# Blank_V3_2.net
KiCad netlist of a schematic drawn in EAGLE
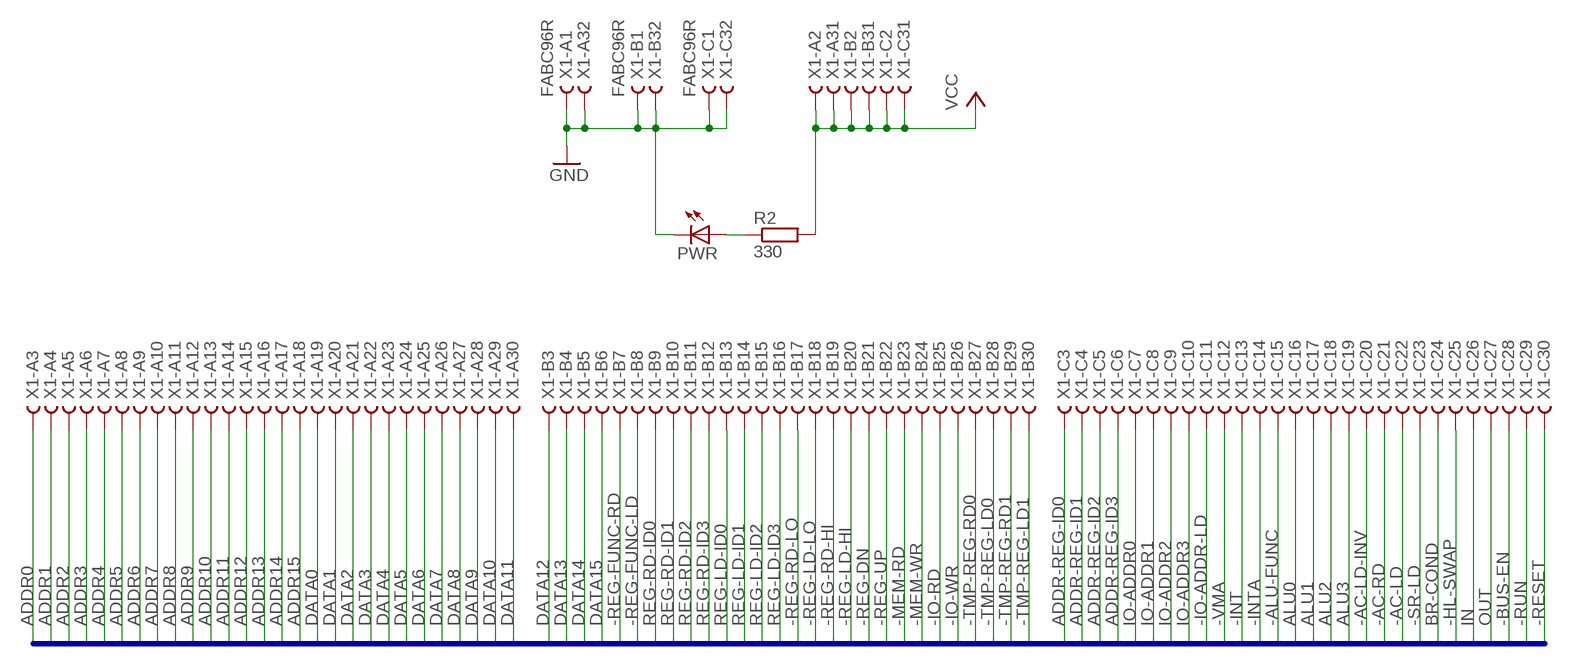
[diagram p0: schematic, sheet 1]

(export (version "E")
  (design (tool "Eeschema 10.0.6"))
  (components
    (comp (ref "PWR")
      (value "LED5MM")
      (footprint "eagle-import:LED5MM")
      (libsource (lib "eagle-import") (part "LED5MM"))
    )
    (comp (ref "R2")
      (value "330")
      (footprint "eagle-import:0207_10")
      (libsource (lib "eagle-import") (part "R0207/10"))
    )
    (comp (ref "X1")
      (value "FABC96R")
      (footprint "eagle-import:FABC96R")
      (libsource (lib "eagle-import") (part "FABC96R"))
    )
  )
  (nets
    (net (code "1") (name "/-AC-LD") (class "Default")
      (node (ref "X1") (pin "C22") (pinfunction "B_C22") (pintype "passive"))
    )
    (net (code "2") (name "/-AC-LD-INV") (class "Default")
      (node (ref "X1") (pin "C20") (pinfunction "B_C20") (pintype "passive"))
    )
    (net (code "3") (name "/-AC-RD") (class "Default")
      (node (ref "X1") (pin "C21") (pinfunction "B_C21") (pintype "passive"))
    )
    (net (code "4") (name "/-ALU-FUNC") (class "Default")
      (node (ref "X1") (pin "C15") (pinfunction "B_C15") (pintype "passive"))
    )
    (net (code "5") (name "/-BUS-EN") (class "Default")
      (node (ref "X1") (pin "C28") (pinfunction "B_C28") (pintype "passive"))
    )
    (net (code "6") (name "/-HL-SWAP") (class "Default")
      (node (ref "X1") (pin "C25") (pinfunction "B_C25") (pintype "passive"))
    )
    (net (code "7") (name "/-INT") (class "Default")
      (node (ref "X1") (pin "C13") (pinfunction "B_C13") (pintype "passive"))
    )
    (net (code "8") (name "/-INTA") (class "Default")
      (node (ref "X1") (pin "C14") (pinfunction "B_C14") (pintype "passive"))
    )
    (net (code "9") (name "/-IO-ADDR-LD") (class "Default")
      (node (ref "X1") (pin "C11") (pinfunction "B_C11") (pintype "passive"))
    )
    (net (code "10") (name "/-IO-RD") (class "Default")
      (node (ref "X1") (pin "B25") (pinfunction "B_B25") (pintype "passive"))
    )
    (net (code "11") (name "/-IO-WR") (class "Default")
      (node (ref "X1") (pin "B26") (pinfunction "B_B26") (pintype "passive"))
    )
    (net (code "12") (name "/-MEM-RD") (class "Default")
      (node (ref "X1") (pin "B23") (pinfunction "B_B23") (pintype "passive"))
    )
    (net (code "13") (name "/-MEM-WR") (class "Default")
      (node (ref "X1") (pin "B24") (pinfunction "B_B24") (pintype "passive"))
    )
    (net (code "14") (name "/-REG-DN") (class "Default")
      (node (ref "X1") (pin "B21") (pinfunction "B_B21") (pintype "passive"))
    )
    (net (code "15") (name "/-REG-FUNC-LD") (class "Default")
      (node (ref "X1") (pin "B8") (pinfunction "B_B8") (pintype "passive"))
    )
    (net (code "16") (name "/-REG-FUNC-RD") (class "Default")
      (node (ref "X1") (pin "B7") (pinfunction "B_B7") (pintype "passive"))
    )
    (net (code "17") (name "/-REG-LD-HI") (class "Default")
      (node (ref "X1") (pin "B20") (pinfunction "B_B20") (pintype "passive"))
    )
    (net (code "18") (name "/-REG-LD-LO") (class "Default")
      (node (ref "X1") (pin "B18") (pinfunction "B_B18") (pintype "passive"))
    )
    (net (code "19") (name "/-REG-RD-HI") (class "Default")
      (node (ref "X1") (pin "B19") (pinfunction "B_B19") (pintype "passive"))
    )
    (net (code "20") (name "/-REG-RD-LO") (class "Default")
      (node (ref "X1") (pin "B17") (pinfunction "B_B17") (pintype "passive"))
    )
    (net (code "21") (name "/-REG-UP") (class "Default")
      (node (ref "X1") (pin "B22") (pinfunction "B_B22") (pintype "passive"))
    )
    (net (code "22") (name "/-RESET") (class "Default")
      (node (ref "X1") (pin "C30") (pinfunction "B_C30") (pintype "passive"))
    )
    (net (code "23") (name "/-RUN") (class "Default")
      (node (ref "X1") (pin "C29") (pinfunction "B_C29") (pintype "passive"))
    )
    (net (code "24") (name "/-SR-LD") (class "Default")
      (node (ref "X1") (pin "C23") (pinfunction "B_C23") (pintype "passive"))
    )
    (net (code "25") (name "/-TMP-REG-LD0") (class "Default")
      (node (ref "X1") (pin "B28") (pinfunction "B_B28") (pintype "passive"))
    )
    (net (code "26") (name "/-TMP-REG-LD1") (class "Default")
      (node (ref "X1") (pin "B30") (pinfunction "B_B30") (pintype "passive"))
    )
    (net (code "27") (name "/-TMP-REG-RD0") (class "Default")
      (node (ref "X1") (pin "B27") (pinfunction "B_B27") (pintype "passive"))
    )
    (net (code "28") (name "/-TMP-REG-RD1") (class "Default")
      (node (ref "X1") (pin "B29") (pinfunction "B_B29") (pintype "passive"))
    )
    (net (code "29") (name "/-VMA") (class "Default")
      (node (ref "X1") (pin "C12") (pinfunction "B_C12") (pintype "passive"))
    )
    (net (code "30") (name "/ADDR-REG-ID0") (class "Default")
      (node (ref "X1") (pin "C3") (pinfunction "B_C3") (pintype "passive"))
    )
    (net (code "31") (name "/ADDR-REG-ID1") (class "Default")
      (node (ref "X1") (pin "C4") (pinfunction "B_C4") (pintype "passive"))
    )
    (net (code "32") (name "/ADDR-REG-ID2") (class "Default")
      (node (ref "X1") (pin "C5") (pinfunction "B_C5") (pintype "passive"))
    )
    (net (code "33") (name "/ADDR-REG-ID3") (class "Default")
      (node (ref "X1") (pin "C6") (pinfunction "B_C6") (pintype "passive"))
    )
    (net (code "34") (name "/ADDR0") (class "Default")
      (node (ref "X1") (pin "A3") (pinfunction "B_A3") (pintype "passive"))
    )
    (net (code "35") (name "/ADDR1") (class "Default")
      (node (ref "X1") (pin "A4") (pinfunction "B_A4") (pintype "passive"))
    )
    (net (code "36") (name "/ADDR2") (class "Default")
      (node (ref "X1") (pin "A5") (pinfunction "B_A5") (pintype "passive"))
    )
    (net (code "37") (name "/ADDR3") (class "Default")
      (node (ref "X1") (pin "A6") (pinfunction "B_A6") (pintype "passive"))
    )
    (net (code "38") (name "/ADDR4") (class "Default")
      (node (ref "X1") (pin "A7") (pinfunction "B_A7") (pintype "passive"))
    )
    (net (code "39") (name "/ADDR5") (class "Default")
      (node (ref "X1") (pin "A8") (pinfunction "B_A8") (pintype "passive"))
    )
    (net (code "40") (name "/ADDR6") (class "Default")
      (node (ref "X1") (pin "A9") (pinfunction "B_A9") (pintype "passive"))
    )
    (net (code "41") (name "/ADDR7") (class "Default")
      (node (ref "X1") (pin "A10") (pinfunction "B_A10") (pintype "passive"))
    )
    (net (code "42") (name "/ADDR8") (class "Default")
      (node (ref "X1") (pin "A11") (pinfunction "B_A11") (pintype "passive"))
    )
    (net (code "43") (name "/ADDR9") (class "Default")
      (node (ref "X1") (pin "A12") (pinfunction "B_A12") (pintype "passive"))
    )
    (net (code "44") (name "/ADDR10") (class "Default")
      (node (ref "X1") (pin "A13") (pinfunction "B_A13") (pintype "passive"))
    )
    (net (code "45") (name "/ADDR11") (class "Default")
      (node (ref "X1") (pin "A14") (pinfunction "B_A14") (pintype "passive"))
    )
    (net (code "46") (name "/ADDR12") (class "Default")
      (node (ref "X1") (pin "A15") (pinfunction "B_A15") (pintype "passive"))
    )
    (net (code "47") (name "/ADDR13") (class "Default")
      (node (ref "X1") (pin "A16") (pinfunction "B_A16") (pintype "passive"))
    )
    (net (code "48") (name "/ADDR14") (class "Default")
      (node (ref "X1") (pin "A17") (pinfunction "B_A17") (pintype "passive"))
    )
    (net (code "49") (name "/ADDR15") (class "Default")
      (node (ref "X1") (pin "A18") (pinfunction "B_A18") (pintype "passive"))
    )
    (net (code "50") (name "/ALU0") (class "Default")
      (node (ref "X1") (pin "C16") (pinfunction "B_C16") (pintype "passive"))
    )
    (net (code "51") (name "/ALU1") (class "Default")
      (node (ref "X1") (pin "C17") (pinfunction "B_C17") (pintype "passive"))
    )
    (net (code "52") (name "/ALU2") (class "Default")
      (node (ref "X1") (pin "C18") (pinfunction "B_C18") (pintype "passive"))
    )
    (net (code "53") (name "/ALU3") (class "Default")
      (node (ref "X1") (pin "C19") (pinfunction "B_C19") (pintype "passive"))
    )
    (net (code "54") (name "/BR-COND") (class "Default")
      (node (ref "X1") (pin "C24") (pinfunction "B_C24") (pintype "passive"))
    )
    (net (code "55") (name "/DATA0") (class "Default")
      (node (ref "X1") (pin "A19") (pinfunction "B_A19") (pintype "passive"))
    )
    (net (code "56") (name "/DATA1") (class "Default")
      (node (ref "X1") (pin "A20") (pinfunction "B_A20") (pintype "passive"))
    )
    (net (code "57") (name "/DATA2") (class "Default")
      (node (ref "X1") (pin "A21") (pinfunction "B_A21") (pintype "passive"))
    )
    (net (code "58") (name "/DATA3") (class "Default")
      (node (ref "X1") (pin "A22") (pinfunction "B_A22") (pintype "passive"))
    )
    (net (code "59") (name "/DATA4") (class "Default")
      (node (ref "X1") (pin "A23") (pinfunction "B_A23") (pintype "passive"))
    )
    (net (code "60") (name "/DATA5") (class "Default")
      (node (ref "X1") (pin "A24") (pinfunction "B_A24") (pintype "passive"))
    )
    (net (code "61") (name "/DATA6") (class "Default")
      (node (ref "X1") (pin "A25") (pinfunction "B_A25") (pintype "passive"))
    )
    (net (code "62") (name "/DATA7") (class "Default")
      (node (ref "X1") (pin "A26") (pinfunction "B_A26") (pintype "passive"))
    )
    (net (code "63") (name "/DATA8") (class "Default")
      (node (ref "X1") (pin "A27") (pinfunction "B_A27") (pintype "passive"))
    )
    (net (code "64") (name "/DATA9") (class "Default")
      (node (ref "X1") (pin "A28") (pinfunction "B_A28") (pintype "passive"))
    )
    (net (code "65") (name "/DATA10") (class "Default")
      (node (ref "X1") (pin "A29") (pinfunction "B_A29") (pintype "passive"))
    )
    (net (code "66") (name "/DATA11") (class "Default")
      (node (ref "X1") (pin "A30") (pinfunction "B_A30") (pintype "passive"))
    )
    (net (code "67") (name "/DATA12") (class "Default")
      (node (ref "X1") (pin "B3") (pinfunction "B_B3") (pintype "passive"))
    )
    (net (code "68") (name "/DATA13") (class "Default")
      (node (ref "X1") (pin "B4") (pinfunction "B_B4") (pintype "passive"))
    )
    (net (code "69") (name "/DATA14") (class "Default")
      (node (ref "X1") (pin "B5") (pinfunction "B_B5") (pintype "passive"))
    )
    (net (code "70") (name "/DATA15") (class "Default")
      (node (ref "X1") (pin "B6") (pinfunction "B_B6") (pintype "passive"))
    )
    (net (code "71") (name "/IN") (class "Default")
      (node (ref "X1") (pin "C26") (pinfunction "B_C26") (pintype "passive"))
    )
    (net (code "72") (name "/IO-ADDR0") (class "Default")
      (node (ref "X1") (pin "C7") (pinfunction "B_C7") (pintype "passive"))
    )
    (net (code "73") (name "/IO-ADDR1") (class "Default")
      (node (ref "X1") (pin "C8") (pinfunction "B_C8") (pintype "passive"))
    )
    (net (code "74") (name "/IO-ADDR2") (class "Default")
      (node (ref "X1") (pin "C9") (pinfunction "B_C9") (pintype "passive"))
    )
    (net (code "75") (name "/IO-ADDR3") (class "Default")
      (node (ref "X1") (pin "C10") (pinfunction "B_C10") (pintype "passive"))
    )
    (net (code "76") (name "/OUT") (class "Default")
      (node (ref "X1") (pin "C27") (pinfunction "B_C27") (pintype "passive"))
    )
    (net (code "77") (name "/REG-LD-ID0") (class "Default")
      (node (ref "X1") (pin "B13") (pinfunction "B_B13") (pintype "passive"))
    )
    (net (code "78") (name "/REG-LD-ID1") (class "Default")
      (node (ref "X1") (pin "B14") (pinfunction "B_B14") (pintype "passive"))
    )
    (net (code "79") (name "/REG-LD-ID2") (class "Default")
      (node (ref "X1") (pin "B15") (pinfunction "B_B15") (pintype "passive"))
    )
    (net (code "80") (name "/REG-LD-ID3") (class "Default")
      (node (ref "X1") (pin "B16") (pinfunction "B_B16") (pintype "passive"))
    )
    (net (code "81") (name "/REG-RD-ID0") (class "Default")
      (node (ref "X1") (pin "B9") (pinfunction "B_B9") (pintype "passive"))
    )
    (net (code "82") (name "/REG-RD-ID1") (class "Default")
      (node (ref "X1") (pin "B10") (pinfunction "B_B10") (pintype "passive"))
    )
    (net (code "83") (name "/REG-RD-ID2") (class "Default")
      (node (ref "X1") (pin "B11") (pinfunction "B_B11") (pintype "passive"))
    )
    (net (code "84") (name "/REG-RD-ID3") (class "Default")
      (node (ref "X1") (pin "B12") (pinfunction "B_B12") (pintype "passive"))
    )
    (net (code "85") (name "GND") (class "Default")
      (node (ref "PWR") (pin "K") (pinfunction "C_K") (pintype "passive"))
      (node (ref "X1") (pin "A1") (pinfunction "B_A1") (pintype "passive"))
      (node (ref "X1") (pin "A32") (pinfunction "B_A32") (pintype "passive"))
      (node (ref "X1") (pin "B1") (pinfunction "B_B1") (pintype "passive"))
      (node (ref "X1") (pin "B32") (pinfunction "B_B32") (pintype "passive"))
      (node (ref "X1") (pin "C1") (pinfunction "B_C1") (pintype "passive"))
      (node (ref "X1") (pin "C32") (pinfunction "B_C32") (pintype "passive"))
    )
    (net (code "86") (name "Net-(PWR-PadA)") (class "Default")
      (node (ref "PWR") (pin "A") (pinfunction "A_A") (pintype "passive"))
      (node (ref "R2") (pin "1") (pinfunction "1_1") (pintype "passive"))
    )
    (net (code "87") (name "VCC") (class "Default")
      (node (ref "R2") (pin "2") (pinfunction "2_2") (pintype "passive"))
      (node (ref "X1") (pin "A2") (pinfunction "B_A2") (pintype "passive"))
      (node (ref "X1") (pin "A31") (pinfunction "B_A31") (pintype "passive"))
      (node (ref "X1") (pin "B2") (pinfunction "B_B2") (pintype "passive"))
      (node (ref "X1") (pin "B31") (pinfunction "B_B31") (pintype "passive"))
      (node (ref "X1") (pin "C2") (pinfunction "B_C2") (pintype "passive"))
      (node (ref "X1") (pin "C31") (pinfunction "B_C31") (pintype "passive"))
    )
  )
)
